# sensing.net
KiCad netlist of a schematic drawn in Altium Designer
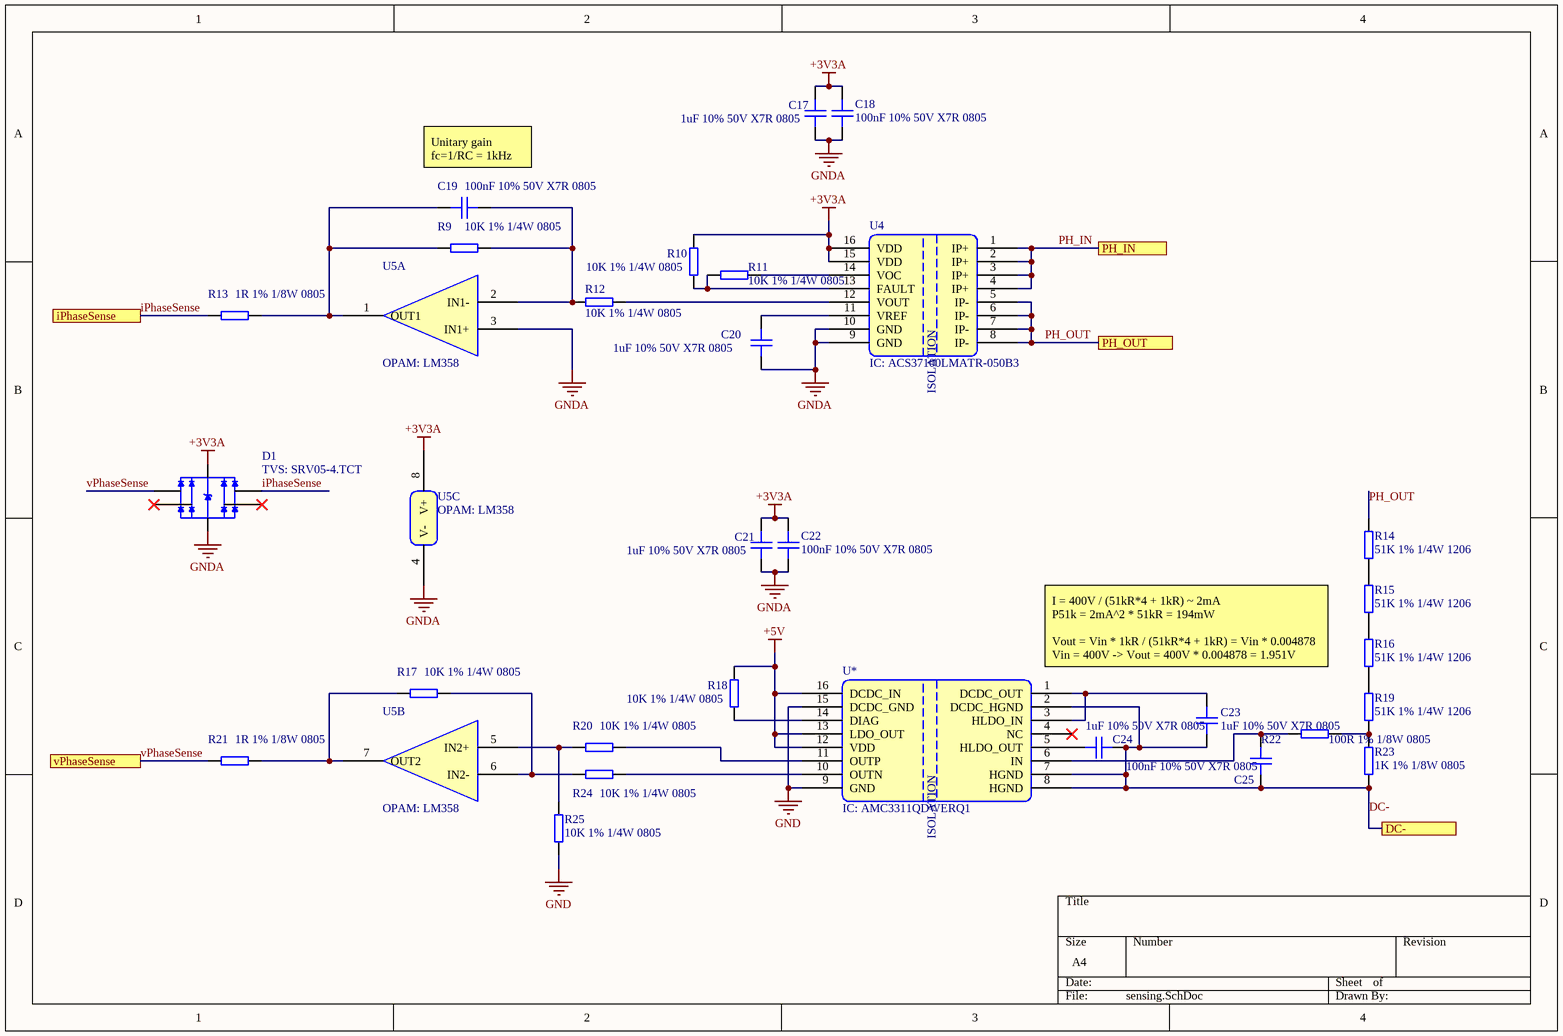
[diagram p0: sensing.SchDoc]

(export (version "E")
  (design (tool "Eeschema 10.0.6"))
  (components
    (comp (ref "C17")
      (value "1uF 10% 50V X7R 0805")
      (footprint "CAPC2012X10N")
      (fields
        (field (name "MANUFACTURER PART NUMBER") "C2012X7R1H105K125AB")
        (field (name "MANUFACTURER") "TDK")
      )
      (libsource (lib "EMEA- E-Tech Racing- I'Escola d'Enginyeria de Barcelona Est") (part "68pF 10 630V C0G 0805"))
    )
    (comp (ref "C18")
      (value "100nF 10% 50V X7R 0805")
      (footprint "CAPC2012X10N")
      (fields
        (field (name "MANUFACTURER") "TDK")
        (field (name "MANUFACTURER PART NUMBER") "C2012X7R1H104K125AM")
      )
      (libsource (lib "EMEA- E-Tech Racing- I'Escola d'Enginyeria de Barcelona Est") (part "68pF 10 630V C0G 0805"))
    )
    (comp (ref "C19")
      (value "100nF 10% 50V X7R 0805")
      (footprint "CAPC2012X10N")
      (fields
        (field (name "MANUFACTURER") "TDK")
        (field (name "MANUFACTURER PART NUMBER") "C2012X7R1H104K125AM")
      )
      (libsource (lib "EMEA- E-Tech Racing- I'Escola d'Enginyeria de Barcelona Est") (part "68pF 10 630V C0G 0805"))
    )
    (comp (ref "C20")
      (value "1uF 10% 50V X7R 0805")
      (footprint "CAPC2012X10N")
      (fields
        (field (name "MANUFACTURER PART NUMBER") "C2012X7R1H105K125AB")
        (field (name "MANUFACTURER") "TDK")
      )
      (libsource (lib "EMEA- E-Tech Racing- I'Escola d'Enginyeria de Barcelona Est") (part "68pF 10 630V C0G 0805"))
    )
    (comp (ref "C21")
      (value "1uF 10% 50V X7R 0805")
      (footprint "CAPC2012X10N")
      (fields
        (field (name "MANUFACTURER PART NUMBER") "C2012X7R1H105K125AB")
        (field (name "MANUFACTURER") "TDK")
      )
      (libsource (lib "EMEA- E-Tech Racing- I'Escola d'Enginyeria de Barcelona Est") (part "68pF 10 630V C0G 0805"))
    )
    (comp (ref "C22")
      (value "100nF 10% 50V X7R 0805")
      (footprint "CAPC2012X10N")
      (fields
        (field (name "MANUFACTURER") "TDK")
        (field (name "MANUFACTURER PART NUMBER") "C2012X7R1H104K125AM")
      )
      (libsource (lib "EMEA- E-Tech Racing- I'Escola d'Enginyeria de Barcelona Est") (part "68pF 10 630V C0G 0805"))
    )
    (comp (ref "C23")
      (value "1uF 10% 50V X7R 0805")
      (footprint "CAPC2012X10N")
      (fields
        (field (name "MANUFACTURER PART NUMBER") "C2012X7R1H105K125AB")
        (field (name "MANUFACTURER") "TDK")
      )
      (libsource (lib "EMEA- E-Tech Racing- I'Escola d'Enginyeria de Barcelona Est") (part "68pF 10 630V C0G 0805"))
    )
    (comp (ref "C24")
      (value "1uF 10% 50V X7R 0805")
      (footprint "CAPC2012X10N")
      (fields
        (field (name "MANUFACTURER PART NUMBER") "C2012X7R1H105K125AB")
        (field (name "MANUFACTURER") "TDK")
      )
      (libsource (lib "EMEA- E-Tech Racing- I'Escola d'Enginyeria de Barcelona Est") (part "68pF 10 630V C0G 0805"))
    )
    (comp (ref "C25")
      (value "100nF 10% 50V X7R 0805")
      (footprint "CAPC2012X10N")
      (fields
        (field (name "MANUFACTURER") "TDK")
        (field (name "MANUFACTURER PART NUMBER") "C2012X7R1H104K125AM")
      )
      (libsource (lib "EMEA- E-Tech Racing- I'Escola d'Enginyeria de Barcelona Est") (part "68pF 10 630V C0G 0805"))
    )
    (comp (ref "D1")
      (value "TVS: SRV05-4.TCT")
      (footprint "SMTC-SOT23-6_V")
      (description "SRV Series 17.5 V 3 pF SMT RailClamp® Low Capacitance TVS Diode Array SOT-23-6")
      (fields (field (name "VOLTAGE") "5V"))
      (libsource (lib "EMEA- E-Tech Racing- I'Escola d'Enginyeria de Barcelona Est") (part "SRV05-4.TCT"))
    )
    (comp (ref "R9")
      (value "10K 1% 1/4W 0805")
      (footprint "RESC2012X05N")
      (description "Res Thick Film 0805 10K Ohm 1% 0.125W ±100ppm/°C Molded SMD Paper T/R")
      (fields
        (field (name "MANUFACTURER") "Stackpole Electronics")
        (field (name "MANUFACTURER PART NUMBER") "RMCF0805FT10K0")
      )
      (libsource (lib "EMEA- E-Tech Racing- I'Escola d'Enginyeria de Barcelona Est") (part "100R 1 1/8W 0805"))
    )
    (comp (ref "R10")
      (value "10K 1% 1/4W 0805")
      (footprint "RESC2012X05N")
      (description "Res Thick Film 0805 10K Ohm 1% 0.125W ±100ppm/°C Molded SMD Paper T/R")
      (fields
        (field (name "MANUFACTURER") "Stackpole Electronics")
        (field (name "MANUFACTURER PART NUMBER") "RMCF0805FT10K0")
      )
      (libsource (lib "EMEA- E-Tech Racing- I'Escola d'Enginyeria de Barcelona Est") (part "100R 1 1/8W 0805"))
    )
    (comp (ref "R11")
      (value "10K 1% 1/4W 0805")
      (footprint "RESC2012X05N")
      (description "Res Thick Film 0805 10K Ohm 1% 0.125W ±100ppm/°C Molded SMD Paper T/R")
      (fields
        (field (name "MANUFACTURER") "Stackpole Electronics")
        (field (name "MANUFACTURER PART NUMBER") "RMCF0805FT10K0")
      )
      (libsource (lib "EMEA- E-Tech Racing- I'Escola d'Enginyeria de Barcelona Est") (part "100R 1 1/8W 0805"))
    )
    (comp (ref "R12")
      (value "10K 1% 1/4W 0805")
      (footprint "RESC2012X05N")
      (description "Res Thick Film 0805 10K Ohm 1% 0.125W ±100ppm/°C Molded SMD Paper T/R")
      (fields
        (field (name "MANUFACTURER") "Stackpole Electronics")
        (field (name "MANUFACTURER PART NUMBER") "RMCF0805FT10K0")
      )
      (libsource (lib "EMEA- E-Tech Racing- I'Escola d'Enginyeria de Barcelona Est") (part "100R 1 1/8W 0805"))
    )
    (comp (ref "R13")
      (value "1R 1% 1/8W 0805")
      (footprint "RESC2012X05N")
      (description "Res Thick Film 0805 1 Ohm 1% 0.125W ±100ppm/°C Molded SMD Paper T/R")
      (fields
        (field (name "MANUFACTURER PART NUMBER") "RMCF0805FT1R00")
        (field (name "MANUFACTURER") "Stackpole Electronics")
      )
      (libsource (lib "EMEA- E-Tech Racing- I'Escola d'Enginyeria de Barcelona Est") (part "100R 1 1/8W 0805"))
    )
    (comp (ref "R14")
      (value "51K 1% 1/4W 1206")
      (footprint "RESC3116X06N")
      (description "Res Thick Film 1206 51K Ohm 1% 0.25W(1/4W) ±100ppm/C Pad SMD T/R Automotive AEC-Q200")
      (fields (field (name "MANUFACTURER") "Stackpole Electronics") (field (name "TOLERANCE") "1%"))
      (libsource (lib "EMEA- E-Tech Racing- I'Escola d'Enginyeria de Barcelona Est") (part "100R 1 1/8W 0805"))
    )
    (comp (ref "R15")
      (value "51K 1% 1/4W 1206")
      (footprint "RESC3116X06N")
      (description "Res Thick Film 1206 51K Ohm 1% 0.25W(1/4W) ±100ppm/C Pad SMD T/R Automotive AEC-Q200")
      (fields (field (name "MANUFACTURER") "Stackpole Electronics") (field (name "TOLERANCE") "1%"))
      (libsource (lib "EMEA- E-Tech Racing- I'Escola d'Enginyeria de Barcelona Est") (part "100R 1 1/8W 0805"))
    )
    (comp (ref "R16")
      (value "51K 1% 1/4W 1206")
      (footprint "RESC3116X06N")
      (description "Res Thick Film 1206 51K Ohm 1% 0.25W(1/4W) ±100ppm/C Pad SMD T/R Automotive AEC-Q200")
      (fields (field (name "MANUFACTURER") "Stackpole Electronics") (field (name "TOLERANCE") "1%"))
      (libsource (lib "EMEA- E-Tech Racing- I'Escola d'Enginyeria de Barcelona Est") (part "100R 1 1/8W 0805"))
    )
    (comp (ref "R17")
      (value "10K 1% 1/4W 0805")
      (footprint "RESC2012X05N")
      (description "Res Thick Film 0805 10K Ohm 1% 0.125W ±100ppm/°C Molded SMD Paper T/R")
      (fields
        (field (name "MANUFACTURER") "Stackpole Electronics")
        (field (name "MANUFACTURER PART NUMBER") "RMCF0805FT10K0")
      )
      (libsource (lib "EMEA- E-Tech Racing- I'Escola d'Enginyeria de Barcelona Est") (part "100R 1 1/8W 0805"))
    )
    (comp (ref "R18")
      (value "10K 1% 1/4W 0805")
      (footprint "RESC2012X05N")
      (description "Res Thick Film 0805 10K Ohm 1% 0.125W ±100ppm/°C Molded SMD Paper T/R")
      (fields
        (field (name "MANUFACTURER") "Stackpole Electronics")
        (field (name "MANUFACTURER PART NUMBER") "RMCF0805FT10K0")
      )
      (libsource (lib "EMEA- E-Tech Racing- I'Escola d'Enginyeria de Barcelona Est") (part "100R 1 1/8W 0805"))
    )
    (comp (ref "R19")
      (value "51K 1% 1/4W 1206")
      (footprint "RESC3116X06N")
      (description "Res Thick Film 1206 51K Ohm 1% 0.25W(1/4W) ±100ppm/C Pad SMD T/R Automotive AEC-Q200")
      (fields (field (name "MANUFACTURER") "Stackpole Electronics") (field (name "TOLERANCE") "1%"))
      (libsource (lib "EMEA- E-Tech Racing- I'Escola d'Enginyeria de Barcelona Est") (part "100R 1 1/8W 0805"))
    )
    (comp (ref "R20")
      (value "10K 1% 1/4W 0805")
      (footprint "RESC2012X05N")
      (description "Res Thick Film 0805 10K Ohm 1% 0.125W ±100ppm/°C Molded SMD Paper T/R")
      (fields
        (field (name "MANUFACTURER") "Stackpole Electronics")
        (field (name "MANUFACTURER PART NUMBER") "RMCF0805FT10K0")
      )
      (libsource (lib "EMEA- E-Tech Racing- I'Escola d'Enginyeria de Barcelona Est") (part "100R 1 1/8W 0805"))
    )
    (comp (ref "R21")
      (value "1R 1% 1/8W 0805")
      (footprint "RESC2012X05N")
      (description "Res Thick Film 0805 1 Ohm 1% 0.125W ±100ppm/°C Molded SMD Paper T/R")
      (fields
        (field (name "MANUFACTURER PART NUMBER") "RMCF0805FT1R00")
        (field (name "MANUFACTURER") "Stackpole Electronics")
      )
      (libsource (lib "EMEA- E-Tech Racing- I'Escola d'Enginyeria de Barcelona Est") (part "100R 1 1/8W 0805"))
    )
    (comp (ref "R22")
      (value "100R 1% 1/8W 0805")
      (footprint "RESC2012X05N")
      (description "Res Thick Film 0805 100 Ohm 1% 0.125W ±100ppm/°C Molded SMD Paper T/R")
      (fields (field (name "TOLERANCE") "1%") (field (name "MANUFACTURER PART NUMBER") "RMCF0805FT100R"))
      (libsource (lib "EMEA- E-Tech Racing- I'Escola d'Enginyeria de Barcelona Est") (part "100R 1 1/8W 0805"))
    )
    (comp (ref "R23")
      (value "1K 1% 1/8W 0805")
      (footprint "RESC2012X05N")
      (description "Res Thick Film 0805 1K Ohm 1% 0.125W ±100ppm/°C Molded SMD Paper T/R")
      (fields (field (name "TOLERANCE") "1%") (field (name "MANUFACTURER") "Stackpole Electronics"))
      (libsource (lib "EMEA- E-Tech Racing- I'Escola d'Enginyeria de Barcelona Est") (part "100R 1 1/8W 0805"))
    )
    (comp (ref "R24")
      (value "10K 1% 1/4W 0805")
      (footprint "RESC2012X05N")
      (description "Res Thick Film 0805 10K Ohm 1% 0.125W ±100ppm/°C Molded SMD Paper T/R")
      (fields
        (field (name "MANUFACTURER") "Stackpole Electronics")
        (field (name "MANUFACTURER PART NUMBER") "RMCF0805FT10K0")
      )
      (libsource (lib "EMEA- E-Tech Racing- I'Escola d'Enginyeria de Barcelona Est") (part "100R 1 1/8W 0805"))
    )
    (comp (ref "R25")
      (value "10K 1% 1/4W 0805")
      (footprint "RESC2012X05N")
      (description "Res Thick Film 0805 10K Ohm 1% 0.125W ±100ppm/°C Molded SMD Paper T/R")
      (fields
        (field (name "MANUFACTURER") "Stackpole Electronics")
        (field (name "MANUFACTURER PART NUMBER") "RMCF0805FT10K0")
      )
      (libsource (lib "EMEA- E-Tech Racing- I'Escola d'Enginyeria de Barcelona Est") (part "100R 1 1/8W 0805"))
    )
    (comp (ref "U*")
      (value "IC: AMC3311QDWERQ1")
      (footprint "SOIC127P1030X265-16N")
      (fields
        (field (name "MANUFACTURER") "Texas Instruments")
        (field (name "MANUFACTURER PART NUMBER") "AMC3311QDWERQ1")
      )
      (libsource (lib "EMEA- E-Tech Racing- I'Escola d'Enginyeria de Barcelona Est") (part "AMC3311"))
    )
    (comp (ref "U4")
      (value "IC: ACS37100LMATR-050B3")
      (footprint "SOIC127P1030X265-16N")
      (description "Magnetoresistive Sensor")
      (fields
        (field (name "MANUFACTURER PART NUMBER") "ACS37100LMATR-050B3")
        (field (name "MANUFACTURER") "Allegro MicroSystems")
      )
      (libsource (lib "EMEA- E-Tech Racing- I'Escola d'Enginyeria de Barcelona Est") (part "ACS37100LMATR-050B3-Symbol-1"))
    )
    (comp (ref "U5")
      (value "OPAM: LM358")
      (footprint "FP-D0008A-IPC_C")
      (description "Dual, 30-V, 700-kHz, 3-mV offset voltage operational amplifier 8-SOIC 0 to 70")
      (fields
        (field (name "MANUFACTURER") "Texas Instruments")
        (field (name "MANUFACTURER PART NUMBER") "LM358BAIDR")
      )
      (libsource (lib "EMEA- E-Tech Racing- I'Escola d'Enginyeria de Barcelona Est") (part "OP{colon} LM358"))
    )
  )
  (nets
    (net (code "1") (name "+3V3A") (class "Default")
      (node (ref "C17") (pin "2") (pinfunction "2_2") (pintype "passive"))
      (node (ref "C18") (pin "2") (pinfunction "2_2") (pintype "passive"))
      (node (ref "C21") (pin "2") (pinfunction "2_2") (pintype "passive"))
      (node (ref "C22") (pin "2") (pinfunction "2_2") (pintype "passive"))
      (node (ref "D1") (pin "5") (pinfunction "5_5") (pintype "passive"))
      (node (ref "R10") (pin "1") (pinfunction "1_1") (pintype "passive"))
      (node (ref "U4") (pin "15") (pinfunction "VDD_15") (pintype "passive"))
      (node (ref "U4") (pin "16") (pinfunction "VDD_16") (pintype "passive"))
      (node (ref "U5") (pin "8") (pinfunction "V+_8") (pintype "passive"))
    )
    (net (code "2") (name "+5V") (class "Default")
      (node (ref "R18") (pin "1") (pinfunction "1_1") (pintype "passive"))
      (node (ref "U*") (pin "12") (pinfunction "VDD_12") (pintype "passive"))
      (node (ref "U*") (pin "13") (pinfunction "LDO_OUT_13") (pintype "passive"))
      (node (ref "U*") (pin "16") (pinfunction "DCDC_IN_16") (pintype "passive"))
    )
    (net (code "3") (name "/DC-") (class "Default")
      (node (ref "C23") (pin "1") (pinfunction "1_1") (pintype "passive"))
      (node (ref "C24") (pin "1") (pinfunction "1_1") (pintype "passive"))
      (node (ref "C25") (pin "1") (pinfunction "1_1") (pintype "passive"))
      (node (ref "R23") (pin "1") (pinfunction "1_1") (pintype "passive"))
      (node (ref "U*") (pin "2") (pinfunction "DCDC_HGND_2") (pintype "passive"))
      (node (ref "U*") (pin "7") (pinfunction "HGND_7") (pintype "passive"))
      (node (ref "U*") (pin "8") (pinfunction "HGND_8") (pintype "passive"))
    )
    (net (code "4") (name "/PH_IN") (class "Default")
      (node (ref "U4") (pin "1") (pinfunction "IP+_1") (pintype "passive"))
      (node (ref "U4") (pin "2") (pinfunction "IP+_2") (pintype "passive"))
      (node (ref "U4") (pin "3") (pinfunction "IP+_3") (pintype "passive"))
      (node (ref "U4") (pin "4") (pinfunction "IP+_4") (pintype "passive"))
    )
    (net (code "5") (name "/PH_OUT") (class "Default")
      (node (ref "R14") (pin "2") (pinfunction "2_2") (pintype "passive"))
      (node (ref "U4") (pin "5") (pinfunction "IP-_5") (pintype "passive"))
      (node (ref "U4") (pin "6") (pinfunction "IP-_6") (pintype "passive"))
      (node (ref "U4") (pin "7") (pinfunction "IP-_7") (pintype "passive"))
      (node (ref "U4") (pin "8") (pinfunction "IP-_8") (pintype "passive"))
    )
    (net (code "6") (name "/iPhaseSense") (class "Default")
      (node (ref "D1") (pin "4") (pinfunction "4_4") (pintype "passive"))
      (node (ref "R13") (pin "1") (pinfunction "1_1") (pintype "passive"))
    )
    (net (code "7") (name "/vPhaseSense") (class "Default")
      (node (ref "D1") (pin "1") (pinfunction "1_1") (pintype "passive"))
      (node (ref "R21") (pin "1") (pinfunction "1_1") (pintype "passive"))
    )
    (net (code "8") (name "GND") (class "Default")
      (node (ref "R25") (pin "1") (pinfunction "1_1") (pintype "passive"))
      (node (ref "U*") (pin "15") (pinfunction "DCDC_GND_15") (pintype "passive"))
      (node (ref "U*") (pin "9") (pinfunction "GND_9") (pintype "passive"))
    )
    (net (code "9") (name "GNDA") (class "Default")
      (node (ref "C17") (pin "1") (pinfunction "1_1") (pintype "passive"))
      (node (ref "C18") (pin "1") (pinfunction "1_1") (pintype "passive"))
      (node (ref "C20") (pin "1") (pinfunction "1_1") (pintype "passive"))
      (node (ref "C21") (pin "1") (pinfunction "1_1") (pintype "passive"))
      (node (ref "C22") (pin "1") (pinfunction "1_1") (pintype "passive"))
      (node (ref "D1") (pin "2") (pinfunction "2_2") (pintype "passive"))
      (node (ref "U4") (pin "10") (pinfunction "GND_10") (pintype "passive"))
      (node (ref "U4") (pin "9") (pinfunction "GND_9") (pintype "passive"))
      (node (ref "U5") (pin "3") (pinfunction "IN1+_3") (pintype "passive"))
      (node (ref "U5") (pin "4") (pinfunction "V-_4") (pintype "passive"))
    )
    (net (code "10") (name "Net-(R14-Pad1)") (class "Default")
      (node (ref "R14") (pin "1") (pinfunction "1_1") (pintype "passive"))
      (node (ref "R15") (pin "2") (pinfunction "2_2") (pintype "passive"))
    )
    (net (code "11") (name "Net-(R15-Pad1)") (class "Default")
      (node (ref "R15") (pin "1") (pinfunction "1_1") (pintype "passive"))
      (node (ref "R16") (pin "2") (pinfunction "2_2") (pintype "passive"))
    )
    (net (code "12") (name "Net-(R16-Pad1)") (class "Default")
      (node (ref "R16") (pin "1") (pinfunction "1_1") (pintype "passive"))
      (node (ref "R19") (pin "2") (pinfunction "2_2") (pintype "passive"))
    )
    (net (code "13") (name "Net-(R19-Pad1)") (class "Default")
      (node (ref "R19") (pin "1") (pinfunction "1_1") (pintype "passive"))
      (node (ref "R22") (pin "1") (pinfunction "1_1") (pintype "passive"))
      (node (ref "R23") (pin "2") (pinfunction "2_2") (pintype "passive"))
    )
    (net (code "14") (name "Net-(U*-DCDC_OUT)") (class "Default")
      (node (ref "C23") (pin "2") (pinfunction "2_2") (pintype "passive"))
      (node (ref "U*") (pin "1") (pinfunction "DCDC_OUT_1") (pintype "passive"))
      (node (ref "U*") (pin "3") (pinfunction "HLDO_IN_3") (pintype "passive"))
    )
    (net (code "15") (name "Net-(U*-DIAG)") (class "Default")
      (node (ref "R18") (pin "2") (pinfunction "2_2") (pintype "passive"))
      (node (ref "U*") (pin "14") (pinfunction "DIAG_14") (pintype "passive"))
    )
    (net (code "16") (name "Net-(U*-HLDO_OUT)") (class "Default")
      (node (ref "C24") (pin "2") (pinfunction "2_2") (pintype "passive"))
      (node (ref "U*") (pin "5") (pinfunction "HLDO_OUT_5") (pintype "passive"))
    )
    (net (code "17") (name "Net-(U*-IN)") (class "Default")
      (node (ref "C25") (pin "2") (pinfunction "2_2") (pintype "passive"))
      (node (ref "R22") (pin "2") (pinfunction "2_2") (pintype "passive"))
      (node (ref "U*") (pin "6") (pinfunction "IN_6") (pintype "passive"))
    )
    (net (code "18") (name "Net-(U*-OUTN)") (class "Default")
      (node (ref "R24") (pin "2") (pinfunction "2_2") (pintype "passive"))
      (node (ref "U*") (pin "10") (pinfunction "OUTN_10") (pintype "passive"))
    )
    (net (code "19") (name "Net-(U*-OUTP)") (class "Default")
      (node (ref "R20") (pin "2") (pinfunction "2_2") (pintype "passive"))
      (node (ref "U*") (pin "11") (pinfunction "OUTP_11") (pintype "passive"))
    )
    (net (code "20") (name "Net-(U4-FAULT)") (class "Default")
      (node (ref "R10") (pin "2") (pinfunction "2_2") (pintype "passive"))
      (node (ref "R11") (pin "1") (pinfunction "1_1") (pintype "passive"))
      (node (ref "U4") (pin "13") (pinfunction "FAULT_13") (pintype "passive"))
    )
    (net (code "21") (name "Net-(U4-VOC)") (class "Default")
      (node (ref "R11") (pin "2") (pinfunction "2_2") (pintype "passive"))
      (node (ref "U4") (pin "14") (pinfunction "VOC_14") (pintype "passive"))
    )
    (net (code "22") (name "Net-(U4-VOUT)") (class "Default")
      (node (ref "R12") (pin "2") (pinfunction "2_2") (pintype "passive"))
      (node (ref "U4") (pin "12") (pinfunction "VOUT_12") (pintype "passive"))
    )
    (net (code "23") (name "Net-(U4-VREF)") (class "Default")
      (node (ref "C20") (pin "2") (pinfunction "2_2") (pintype "passive"))
      (node (ref "U4") (pin "11") (pinfunction "VREF_11") (pintype "passive"))
    )
    (net (code "24") (name "Net-(U5A-IN1-)") (class "Default")
      (node (ref "C19") (pin "2") (pinfunction "2_2") (pintype "passive"))
      (node (ref "R12") (pin "1") (pinfunction "1_1") (pintype "passive"))
      (node (ref "R9") (pin "2") (pinfunction "2_2") (pintype "passive"))
      (node (ref "U5") (pin "2") (pinfunction "IN1-_2") (pintype "passive"))
    )
    (net (code "25") (name "Net-(U5A-OUT1)") (class "Default")
      (node (ref "C19") (pin "1") (pinfunction "1_1") (pintype "passive"))
      (node (ref "R13") (pin "2") (pinfunction "2_2") (pintype "passive"))
      (node (ref "R9") (pin "1") (pinfunction "1_1") (pintype "passive"))
      (node (ref "U5") (pin "1") (pinfunction "OUT1_1") (pintype "passive"))
    )
    (net (code "26") (name "Net-(U5B-IN2+)") (class "Default")
      (node (ref "R20") (pin "1") (pinfunction "1_1") (pintype "passive"))
      (node (ref "R25") (pin "2") (pinfunction "2_2") (pintype "passive"))
      (node (ref "U5") (pin "5") (pinfunction "IN2+_5") (pintype "passive"))
    )
    (net (code "27") (name "Net-(U5B-IN2-)") (class "Default")
      (node (ref "R17") (pin "2") (pinfunction "2_2") (pintype "passive"))
      (node (ref "R24") (pin "1") (pinfunction "1_1") (pintype "passive"))
      (node (ref "U5") (pin "6") (pinfunction "IN2-_6") (pintype "passive"))
    )
    (net (code "28") (name "Net-(U5B-OUT2)") (class "Default")
      (node (ref "R17") (pin "1") (pinfunction "1_1") (pintype "passive"))
      (node (ref "R21") (pin "2") (pinfunction "2_2") (pintype "passive"))
      (node (ref "U5") (pin "7") (pinfunction "OUT2_7") (pintype "passive"))
    )
    (net (code "29") (name "unconnected-(D1-Pad3)") (class "Default")
      (node (ref "D1") (pin "3") (pinfunction "3_3") (pintype "passive+no_connect"))
    )
    (net (code "30") (name "unconnected-(D1-Pad6)") (class "Default")
      (node (ref "D1") (pin "6") (pinfunction "6_6") (pintype "passive+no_connect"))
    )
    (net (code "31") (name "unconnected-(U*-NC-Pad4)") (class "Default")
      (node (ref "U*") (pin "4") (pinfunction "NC_4") (pintype "passive+no_connect"))
    )
  )
)
